# MoistureBoard_v1.net
KiCad netlist of a schematic drawn in Altium Designer
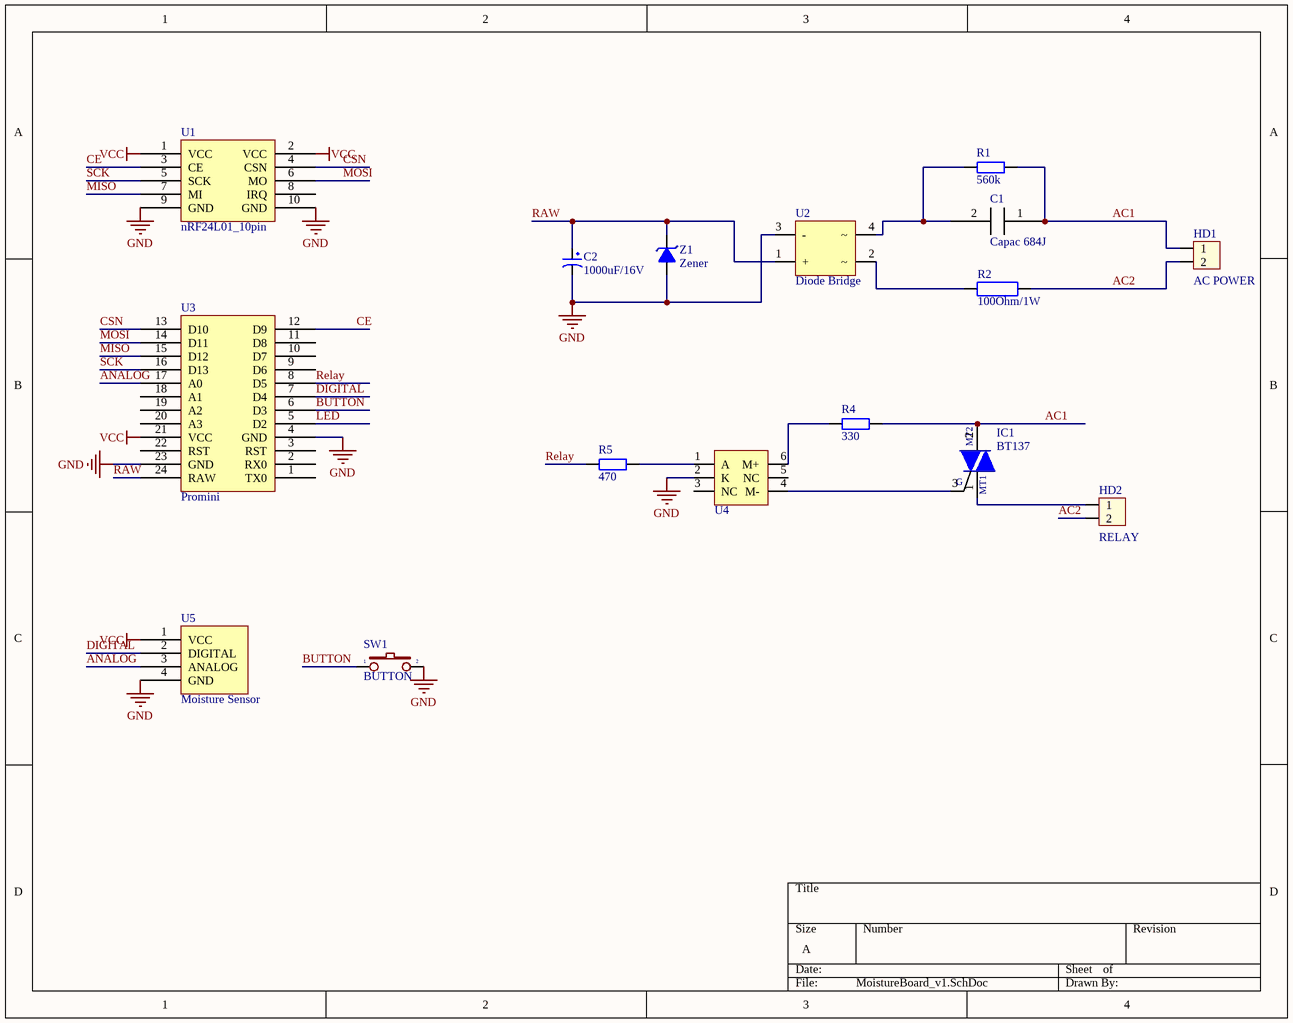
[diagram p0: MoistureBoard_v1.SchDoc]

(export (version "E")
  (design (tool "Eeschema 10.0.6"))
  (components
    (comp (ref "C1")
      (value "Capac 684J")
      (footprint "Tu keo 684J 400V")
      (libsource (lib "myLibs") (part "Tu keo 684J 400V"))
    )
    (comp (ref "C2")
      (value "1000uF/16V")
      (footprint "CP2/4")
      (description "Cap 2200uF/16V - 1000uF/50V")
      (libsource (lib "myLibs") (part "CP5"))
    )
    (comp (ref "HD1")
      (value "AC POWER")
      (footprint "HED2")
      (description "Header 2 (Green)")
      (libsource (lib "syhaunguyen") (part "Hed2"))
    )
    (comp (ref "HD2")
      (value "RELAY")
      (footprint "HED2")
      (description "Header 2 (Green)")
      (libsource (lib "syhaunguyen") (part "Hed2"))
    )
    (comp (ref "IC1")
      (value "BT137")
      (footprint "QTO-220")
      (description "Triacs - 8A")
      (libsource (lib "myLibs") (part "BT137"))
    )
    (comp (ref "R1")
      (value "560k")
      (footprint "R1/4W")
      (description "Resistor 1/4W")
      (libsource (lib "myLibs") (part "R1/4W"))
    )
    (comp (ref "R2")
      (value "100Ohm/1W")
      (footprint "RES1W")
      (description "1W Res Power")
      (fields (field (name "CREATOR") "Nguyen Ba Bien"))
      (libsource (lib "myLibs") (part "Res 1W"))
    )
    (comp (ref "R4")
      (value "330")
      (footprint "R1/4W")
      (description "Resistor 1/4W")
      (libsource (lib "myLibs") (part "R1/4W"))
    )
    (comp (ref "R5")
      (value "470")
      (footprint "R1/4W")
      (description "Resistor 1/4W")
      (libsource (lib "myLibs") (part "R1/4W"))
    )
    (comp (ref "SW1")
      (value "BUTTON")
      (footprint "SW2")
      (description "Switch button 2 pin")
      (libsource (lib "syhaunguyen") (part "SW2"))
    )
    (comp (ref "U1")
      (value "nRF24L01_10pin")
      (footprint "NRF24L01_10PIN")
      (libsource (lib "myLibs") (part "nRF24L01_10pin"))
    )
    (comp (ref "U2")
      (value "Diode Bridge")
      (footprint "DIODE BRIDGE")
      (libsource (lib "myLibs") (part "Diode Bridge"))
    )
    (comp (ref "U3") (value "Promini") (footprint "Promini") (libsource (lib "myLibs") (part "Promini")))
    (comp (ref "U4") (value "MOC3021M") (footprint "MOC30XX") (libsource (lib "myLibs") (part "MOC3021M")))
    (comp (ref "U5")
      (value "Moisture Sensor")
      (footprint "MOISTURE")
      (libsource (lib "myLibs") (part "Moisture Sensor"))
    )
    (comp (ref "Z1") (value "Zener") (footprint "D1A") (libsource (lib "myLibs") (part "Zener")))
  )
  (nets
    (net (code "1") (name "/AC1") (class "Default")
      (node (ref "C1") (pin "1") (pinfunction "1_1") (pintype "passive"))
      (node (ref "HD1") (pin "1") (pinfunction "1_1") (pintype "passive"))
      (node (ref "IC1") (pin "2") (pinfunction "MT2_2") (pintype "passive"))
      (node (ref "R1") (pin "2") (pinfunction "2_2") (pintype "passive"))
      (node (ref "R4") (pin "2") (pinfunction "2_2") (pintype "passive"))
    )
    (net (code "2") (name "/AC2") (class "Default")
      (node (ref "HD1") (pin "2") (pinfunction "2_2") (pintype "passive"))
      (node (ref "HD2") (pin "2") (pinfunction "2_2") (pintype "passive"))
      (node (ref "R2") (pin "2") (pinfunction "2_2") (pintype "passive"))
    )
    (net (code "3") (name "/ANALOG") (class "Default")
      (node (ref "U3") (pin "17") (pinfunction "A0_17") (pintype "passive"))
      (node (ref "U5") (pin "3") (pinfunction "ANALOG_3") (pintype "passive"))
    )
    (net (code "4") (name "/BUTTON") (class "Default")
      (node (ref "SW1") (pin "1") (pinfunction "1_1") (pintype "passive"))
      (node (ref "U3") (pin "6") (pinfunction "D3_6") (pintype "passive"))
    )
    (net (code "5") (name "/CE") (class "Default")
      (node (ref "U1") (pin "3") (pinfunction "CE_3") (pintype "passive"))
      (node (ref "U3") (pin "12") (pinfunction "D9_12") (pintype "passive"))
    )
    (net (code "6") (name "/CSN") (class "Default")
      (node (ref "U1") (pin "4") (pinfunction "CSN_4") (pintype "passive"))
      (node (ref "U3") (pin "13") (pinfunction "D10_13") (pintype "passive"))
    )
    (net (code "7") (name "/DIGITAL") (class "Default")
      (node (ref "U3") (pin "7") (pinfunction "D4_7") (pintype "passive"))
      (node (ref "U5") (pin "2") (pinfunction "DIGITAL_2") (pintype "passive"))
    )
    (net (code "8") (name "/LED") (class "Default")
      (node (ref "U3") (pin "5") (pinfunction "D2_5") (pintype "passive"))
    )
    (net (code "9") (name "/MISO") (class "Default")
      (node (ref "U1") (pin "7") (pinfunction "MI_7") (pintype "passive"))
      (node (ref "U3") (pin "15") (pinfunction "D12_15") (pintype "passive"))
    )
    (net (code "10") (name "/MOSI") (class "Default")
      (node (ref "U1") (pin "6") (pinfunction "MO_6") (pintype "passive"))
      (node (ref "U3") (pin "14") (pinfunction "D11_14") (pintype "passive"))
    )
    (net (code "11") (name "/RAW") (class "Default")
      (node (ref "C2") (pin "1") (pinfunction "1_1") (pintype "passive"))
      (node (ref "U2") (pin "1") (pinfunction "+_1") (pintype "passive"))
      (node (ref "U3") (pin "24") (pinfunction "RAW_24") (pintype "passive"))
      (node (ref "Z1") (pin "2") (pinfunction "K_2") (pintype "passive"))
    )
    (net (code "12") (name "/Relay") (class "Default")
      (node (ref "R5") (pin "1") (pinfunction "1_1") (pintype "passive"))
      (node (ref "U3") (pin "8") (pinfunction "D5_8") (pintype "passive"))
    )
    (net (code "13") (name "/SCK") (class "Default")
      (node (ref "U1") (pin "5") (pinfunction "SCK_5") (pintype "passive"))
      (node (ref "U3") (pin "16") (pinfunction "D13_16") (pintype "passive"))
    )
    (net (code "14") (name "GND") (class "Default")
      (node (ref "C2") (pin "2") (pinfunction "2_2") (pintype "passive"))
      (node (ref "SW1") (pin "2") (pinfunction "2_2") (pintype "passive"))
      (node (ref "U1") (pin "10") (pinfunction "GND_10") (pintype "passive"))
      (node (ref "U1") (pin "9") (pinfunction "GND_9") (pintype "passive"))
      (node (ref "U2") (pin "3") (pinfunction "-_3") (pintype "passive"))
      (node (ref "U3") (pin "23") (pinfunction "GND_23") (pintype "passive"))
      (node (ref "U3") (pin "4") (pinfunction "GND_4") (pintype "passive"))
      (node (ref "U4") (pin "2") (pinfunction "K_2") (pintype "passive"))
      (node (ref "U5") (pin "4") (pinfunction "GND_4") (pintype "passive"))
      (node (ref "Z1") (pin "1") (pinfunction "A_1") (pintype "passive"))
    )
    (net (code "15") (name "Net-(C1-Pad2)") (class "Default")
      (node (ref "C1") (pin "2") (pinfunction "2_2") (pintype "passive"))
      (node (ref "R1") (pin "1") (pinfunction "1_1") (pintype "passive"))
      (node (ref "U2") (pin "4") (pinfunction "~_4") (pintype "passive"))
    )
    (net (code "16") (name "Net-(IC1-IN)") (class "Default")
      (node (ref "IC1") (pin "3") (pinfunction "IN_3") (pintype "passive"))
      (node (ref "U4") (pin "4") (pinfunction "M-_4") (pintype "passive"))
    )
    (net (code "17") (name "Net-(IC1-MT1)") (class "Default")
      (node (ref "HD2") (pin "1") (pinfunction "1_1") (pintype "passive"))
      (node (ref "IC1") (pin "1") (pinfunction "MT1_1") (pintype "passive"))
    )
    (net (code "18") (name "Net-(R2-Pad1)") (class "Default")
      (node (ref "R2") (pin "1") (pinfunction "1_1") (pintype "passive"))
      (node (ref "U2") (pin "2") (pinfunction "~_2") (pintype "passive"))
    )
    (net (code "19") (name "Net-(U4-A)") (class "Default")
      (node (ref "R5") (pin "2") (pinfunction "2_2") (pintype "passive"))
      (node (ref "U4") (pin "1") (pinfunction "A_1") (pintype "passive"))
    )
    (net (code "20") (name "Net-(U4-M+)") (class "Default")
      (node (ref "R4") (pin "1") (pinfunction "1_1") (pintype "passive"))
      (node (ref "U4") (pin "6") (pinfunction "M+_6") (pintype "passive"))
    )
    (net (code "21") (name "VCC") (class "Default")
      (node (ref "U1") (pin "1") (pinfunction "VCC_1") (pintype "passive"))
      (node (ref "U1") (pin "2") (pinfunction "VCC_2") (pintype "passive"))
      (node (ref "U3") (pin "21") (pinfunction "VCC_21") (pintype "passive"))
      (node (ref "U5") (pin "1") (pinfunction "VCC_1") (pintype "passive"))
    )
    (net (code "22") (name "unconnected-(U1-IRQ-Pad8)") (class "Default")
      (node (ref "U1") (pin "8") (pinfunction "IRQ_8") (pintype "passive"))
    )
    (net (code "23") (name "unconnected-(U3-A1-Pad18)") (class "Default")
      (node (ref "U3") (pin "18") (pinfunction "A1_18") (pintype "passive"))
    )
    (net (code "24") (name "unconnected-(U3-A2-Pad19)") (class "Default")
      (node (ref "U3") (pin "19") (pinfunction "A2_19") (pintype "passive"))
    )
    (net (code "25") (name "unconnected-(U3-A3-Pad20)") (class "Default")
      (node (ref "U3") (pin "20") (pinfunction "A3_20") (pintype "passive"))
    )
    (net (code "26") (name "unconnected-(U3-D6-Pad9)") (class "Default")
      (node (ref "U3") (pin "9") (pinfunction "D6_9") (pintype "passive"))
    )
    (net (code "27") (name "unconnected-(U3-D7-Pad10)") (class "Default")
      (node (ref "U3") (pin "10") (pinfunction "D7_10") (pintype "passive"))
    )
    (net (code "28") (name "unconnected-(U3-D8-Pad11)") (class "Default")
      (node (ref "U3") (pin "11") (pinfunction "D8_11") (pintype "passive"))
    )
    (net (code "29") (name "unconnected-(U3-RST-Pad3)") (class "Default")
      (node (ref "U3") (pin "3") (pinfunction "RST_3") (pintype "passive"))
    )
    (net (code "30") (name "unconnected-(U3-RST-Pad22)") (class "Default")
      (node (ref "U3") (pin "22") (pinfunction "RST_22") (pintype "passive"))
    )
    (net (code "31") (name "unconnected-(U3-RX0-Pad2)") (class "Default")
      (node (ref "U3") (pin "2") (pinfunction "RX0_2") (pintype "passive"))
    )
    (net (code "32") (name "unconnected-(U3-TX0-Pad1)") (class "Default")
      (node (ref "U3") (pin "1") (pinfunction "TX0_1") (pintype "passive"))
    )
    (net (code "33") (name "unconnected-(U4-NC-Pad3)") (class "Default")
      (node (ref "U4") (pin "3") (pinfunction "NC_3") (pintype "passive"))
    )
    (net (code "34") (name "unconnected-(U4-NC-Pad5)") (class "Default")
      (node (ref "U4") (pin "5") (pinfunction "NC_5") (pintype "passive"))
    )
  )
)
